# MB_DoorLock.net
KiCad netlist of a schematic drawn in EAGLE
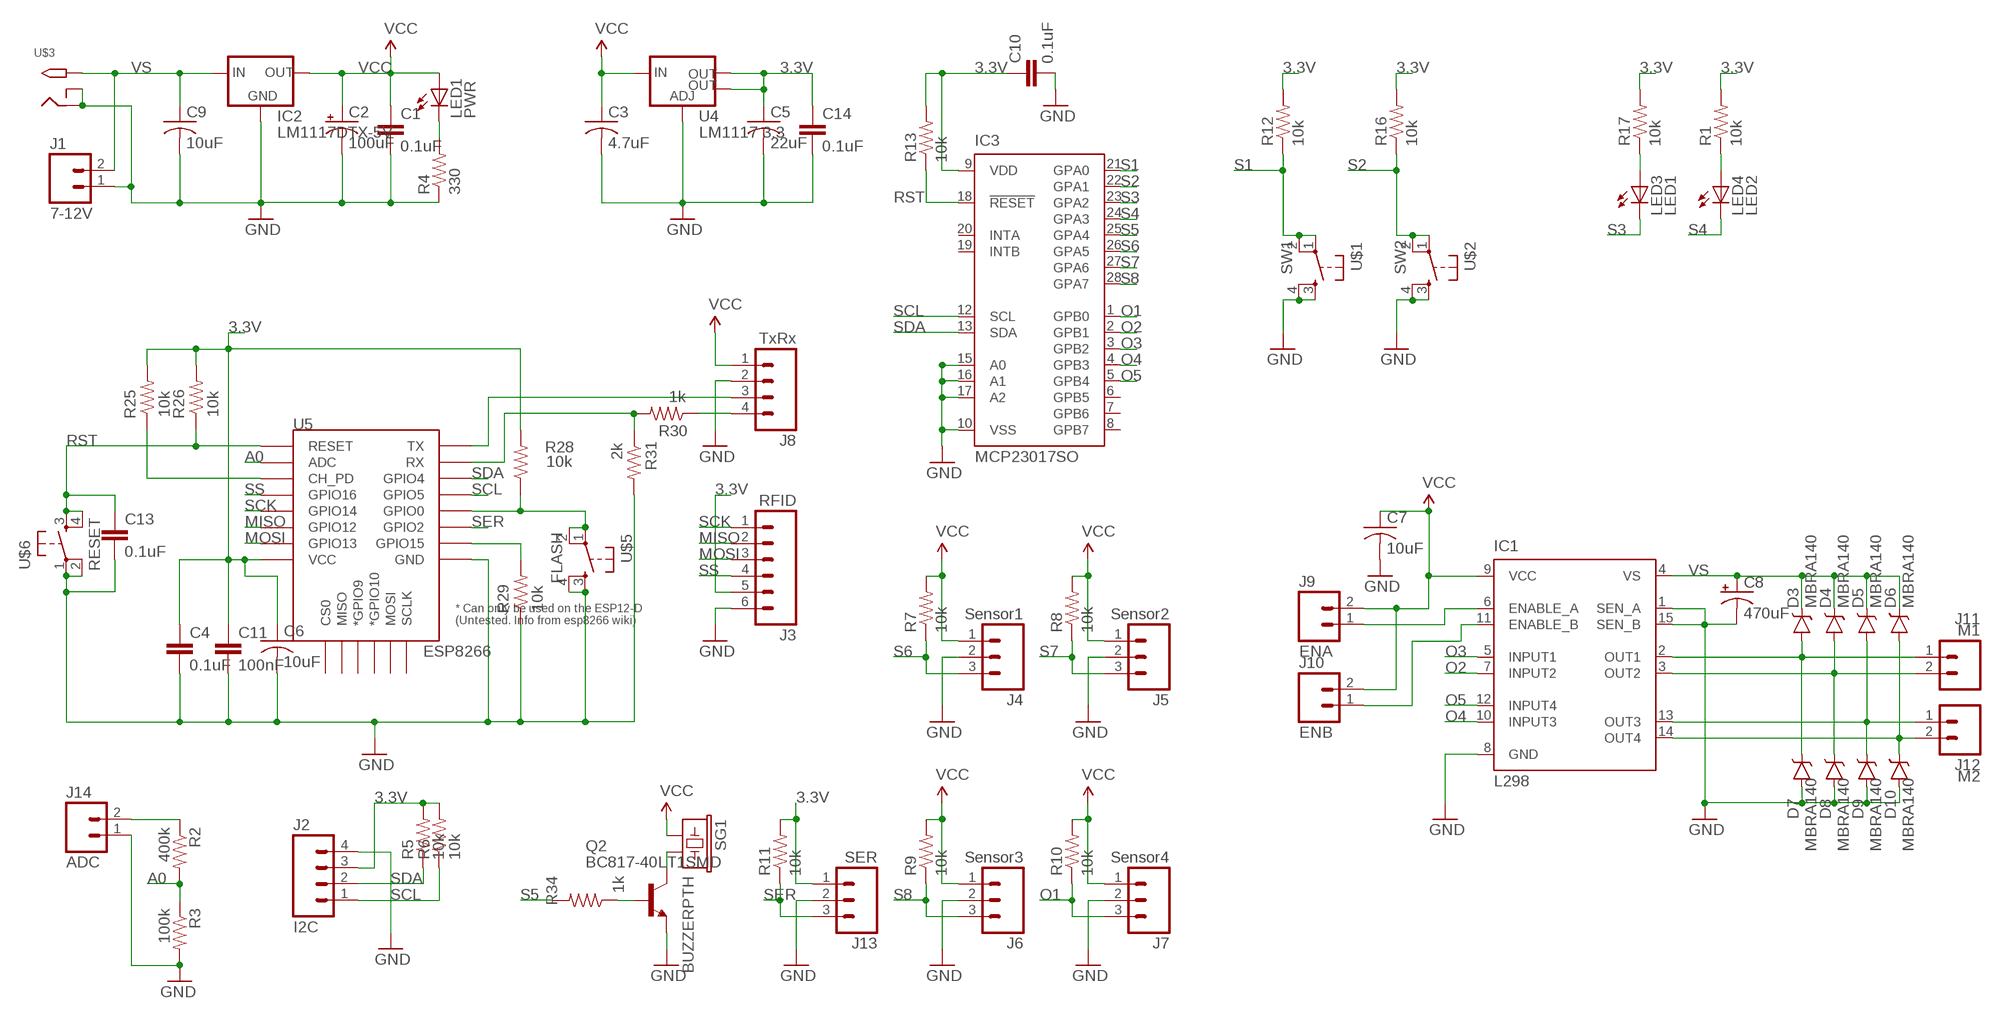
[diagram p0: schematic, sheet 1]

(export (version "E")
  (design (tool "Eeschema 10.0.6"))
  (components
    (comp (ref "C1")
      (value "0.1uF")
      (footprint "eagle-import:0805")
      (libsource (lib "eagle-import") (part "CAP0805"))
    )
    (comp (ref "C2")
      (value "100uF")
      (footprint "eagle-import:EIA3528-KIT")
      (libsource (lib "eagle-import") (part "CAP_POL3528-KIT"))
    )
    (comp (ref "C3")
      (value "4.7uF")
      (footprint "eagle-import:C1206")
      (libsource (lib "eagle-import") (part "C-USC1206"))
    )
    (comp (ref "C4")
      (value "0.1uF")
      (footprint "eagle-import:0805")
      (libsource (lib "eagle-import") (part "CAP0805"))
    )
    (comp (ref "C5")
      (value "22uF")
      (footprint "eagle-import:C1206")
      (libsource (lib "eagle-import") (part "C-USC1206"))
    )
    (comp (ref "C6")
      (value "10uF")
      (footprint "eagle-import:C1206")
      (libsource (lib "eagle-import") (part "C-USC1206"))
    )
    (comp (ref "C7")
      (value "10uF")
      (footprint "eagle-import:C1206")
      (libsource (lib "eagle-import") (part "C-USC1206"))
    )
    (comp (ref "C8")
      (value "470uF")
      (footprint "eagle-import:153CLV-1012")
      (libsource (lib "eagle-import") (part "CPOL-US153CLV-1012"))
    )
    (comp (ref "C9")
      (value "10uF")
      (footprint "eagle-import:C1206")
      (libsource (lib "eagle-import") (part "C-USC1206"))
    )
    (comp (ref "C10")
      (value "0.1uF")
      (footprint "eagle-import:0805")
      (libsource (lib "eagle-import") (part "CAP0805"))
    )
    (comp (ref "C11")
      (value "100nF")
      (footprint "eagle-import:0805")
      (libsource (lib "eagle-import") (part "CAP0805"))
    )
    (comp (ref "C13")
      (value "0.1uF")
      (footprint "eagle-import:0805")
      (libsource (lib "eagle-import") (part "CAP0805"))
    )
    (comp (ref "C14")
      (value "0.1uF")
      (footprint "eagle-import:0805")
      (libsource (lib "eagle-import") (part "CAP0805"))
    )
    (comp (ref "D3")
      (value "MBRA140")
      (footprint "eagle-import:SMA-DIODE")
      (libsource (lib "eagle-import") (part "MBRA140"))
    )
    (comp (ref "D4")
      (value "MBRA140")
      (footprint "eagle-import:SMA-DIODE")
      (libsource (lib "eagle-import") (part "MBRA140"))
    )
    (comp (ref "D5")
      (value "MBRA140")
      (footprint "eagle-import:SMA-DIODE")
      (libsource (lib "eagle-import") (part "MBRA140"))
    )
    (comp (ref "D6")
      (value "MBRA140")
      (footprint "eagle-import:SMA-DIODE")
      (libsource (lib "eagle-import") (part "MBRA140"))
    )
    (comp (ref "D7")
      (value "MBRA140")
      (footprint "eagle-import:SMA-DIODE")
      (libsource (lib "eagle-import") (part "MBRA140"))
    )
    (comp (ref "D8")
      (value "MBRA140")
      (footprint "eagle-import:SMA-DIODE")
      (libsource (lib "eagle-import") (part "MBRA140"))
    )
    (comp (ref "D9")
      (value "MBRA140")
      (footprint "eagle-import:SMA-DIODE")
      (libsource (lib "eagle-import") (part "MBRA140"))
    )
    (comp (ref "D10")
      (value "MBRA140")
      (footprint "eagle-import:SMA-DIODE")
      (libsource (lib "eagle-import") (part "MBRA140"))
    )
    (comp (ref "IC1")
      (value "L298")
      (footprint "eagle-import:MULTIWATT-15")
      (libsource (lib "eagle-import") (part "L298"))
    )
    (comp (ref "IC2")
      (value "LM1117DTX-5V")
      (footprint "eagle-import:TO252")
      (libsource (lib "eagle-import") (part "LM1117DTX-3.3"))
    )
    (comp (ref "IC3")
      (value "MCP23017SO")
      (footprint "eagle-import:SO28W")
      (fields (field (name "MF") "MICROCHIP") (field (name "MPN") "MCP23017-E/SO"))
      (libsource (lib "eagle-import") (part "MCP23017SO"))
    )
    (comp (ref "J1")
      (value "7-12V")
      (footprint "eagle-import:MOLEX-1X2")
      (libsource (lib "eagle-import") (part "M02POLAR"))
    )
    (comp (ref "J2")
      (value "I2C")
      (footprint "eagle-import:JST-4-PTH-VERT")
      (libsource (lib "eagle-import") (part "M04JST-PTH-VERT"))
    )
    (comp (ref "J3")
      (value "RFID")
      (footprint "eagle-import:MOLEX-1X6")
      (libsource (lib "eagle-import") (part "M06POLAR"))
    )
    (comp (ref "J4")
      (value "Sensor1")
      (footprint "eagle-import:JST-3-PTH-VERT")
      (libsource (lib "eagle-import") (part "M03JST-PTH-VERT"))
    )
    (comp (ref "J5")
      (value "Sensor2")
      (footprint "eagle-import:JST-3-PTH-VERT")
      (libsource (lib "eagle-import") (part "M03JST-PTH-VERT"))
    )
    (comp (ref "J6")
      (value "Sensor3")
      (footprint "eagle-import:JST-3-PTH-VERT")
      (libsource (lib "eagle-import") (part "M03JST-PTH-VERT"))
    )
    (comp (ref "J7")
      (value "Sensor4")
      (footprint "eagle-import:JST-3-PTH-VERT")
      (libsource (lib "eagle-import") (part "M03JST-PTH-VERT"))
    )
    (comp (ref "J8")
      (value "TxRx")
      (footprint "eagle-import:MOLEX-1X4")
      (libsource (lib "eagle-import") (part "M04POLAR"))
    )
    (comp (ref "J9")
      (value "ENA")
      (footprint "eagle-import:1X02")
      (libsource (lib "eagle-import") (part "M02PTH"))
    )
    (comp (ref "J10")
      (value "ENB")
      (footprint "eagle-import:1X02")
      (libsource (lib "eagle-import") (part "M02PTH"))
    )
    (comp (ref "J11")
      (value "M1")
      (footprint "eagle-import:MOLEX-1X2")
      (libsource (lib "eagle-import") (part "M02POLAR"))
    )
    (comp (ref "J12")
      (value "M2")
      (footprint "eagle-import:MOLEX-1X2")
      (libsource (lib "eagle-import") (part "M02POLAR"))
    )
    (comp (ref "J13")
      (value "SER")
      (footprint "eagle-import:JST-3-PTH-VERT")
      (libsource (lib "eagle-import") (part "M03JST-PTH-VERT"))
    )
    (comp (ref "J14")
      (value "ADC")
      (footprint "eagle-import:MOLEX-1X2")
      (libsource (lib "eagle-import") (part "M02POLAR"))
    )
    (comp (ref "LED1")
      (value "PWR")
      (footprint "eagle-import:CHIP-LED0805")
      (libsource (lib "eagle-import") (part "LEDCHIP-LED0805"))
    )
    (comp (ref "LED3")
      (value "LED1")
      (footprint "eagle-import:CHIP-LED0805")
      (libsource (lib "eagle-import") (part "LEDCHIP-LED0805"))
    )
    (comp (ref "LED4")
      (value "LED2")
      (footprint "eagle-import:CHIP-LED0805")
      (libsource (lib "eagle-import") (part "LEDCHIP-LED0805"))
    )
    (comp (ref "Q2")
      (value "BC817-40LT1SMD")
      (footprint "eagle-import:SOT23-BEC")
      (libsource (lib "eagle-import") (part "BC817SMD-40LT1"))
    )
    (comp (ref "R1")
      (value "10k")
      (footprint "eagle-import:0805")
      (libsource (lib "eagle-import") (part "RESISTOR0805-RES"))
    )
    (comp (ref "R2")
      (value "400k")
      (footprint "eagle-import:0805")
      (libsource (lib "eagle-import") (part "RESISTOR0805-RES"))
    )
    (comp (ref "R3")
      (value "100k")
      (footprint "eagle-import:0805")
      (libsource (lib "eagle-import") (part "RESISTOR0805-RES"))
    )
    (comp (ref "R4")
      (value "330")
      (footprint "eagle-import:0805")
      (libsource (lib "eagle-import") (part "RESISTOR0805-RES"))
    )
    (comp (ref "R5")
      (value "10k")
      (footprint "eagle-import:0805")
      (libsource (lib "eagle-import") (part "RESISTOR0805-RES"))
    )
    (comp (ref "R6")
      (value "10k")
      (footprint "eagle-import:0805")
      (libsource (lib "eagle-import") (part "RESISTOR0805-RES"))
    )
    (comp (ref "R7")
      (value "10k")
      (footprint "eagle-import:0805")
      (libsource (lib "eagle-import") (part "RESISTOR0805-RES"))
    )
    (comp (ref "R8")
      (value "10k")
      (footprint "eagle-import:0805")
      (libsource (lib "eagle-import") (part "RESISTOR0805-RES"))
    )
    (comp (ref "R9")
      (value "10k")
      (footprint "eagle-import:0805")
      (libsource (lib "eagle-import") (part "RESISTOR0805-RES"))
    )
    (comp (ref "R10")
      (value "10k")
      (footprint "eagle-import:0805")
      (libsource (lib "eagle-import") (part "RESISTOR0805-RES"))
    )
    (comp (ref "R11")
      (value "10k")
      (footprint "eagle-import:0805")
      (libsource (lib "eagle-import") (part "RESISTOR0805-RES"))
    )
    (comp (ref "R12")
      (value "10k")
      (footprint "eagle-import:0805")
      (libsource (lib "eagle-import") (part "RESISTOR0805-RES"))
    )
    (comp (ref "R13")
      (value "10k")
      (footprint "eagle-import:0805")
      (libsource (lib "eagle-import") (part "RESISTOR0805-RES"))
    )
    (comp (ref "R16")
      (value "10k")
      (footprint "eagle-import:0805")
      (libsource (lib "eagle-import") (part "RESISTOR0805-RES"))
    )
    (comp (ref "R17")
      (value "10k")
      (footprint "eagle-import:0805")
      (libsource (lib "eagle-import") (part "RESISTOR0805-RES"))
    )
    (comp (ref "R25")
      (value "10k")
      (footprint "eagle-import:0805")
      (libsource (lib "eagle-import") (part "RESISTOR0805-RES"))
    )
    (comp (ref "R26")
      (value "10k")
      (footprint "eagle-import:0805")
      (libsource (lib "eagle-import") (part "RESISTOR0805-RES"))
    )
    (comp (ref "R28")
      (value "10k")
      (footprint "eagle-import:0805")
      (libsource (lib "eagle-import") (part "RESISTOR0805-RES"))
    )
    (comp (ref "R29")
      (value "10k")
      (footprint "eagle-import:0805")
      (libsource (lib "eagle-import") (part "RESISTOR0805-RES"))
    )
    (comp (ref "R30")
      (value "1k")
      (footprint "eagle-import:0805")
      (libsource (lib "eagle-import") (part "RESISTOR0805-RES"))
    )
    (comp (ref "R31")
      (value "2k")
      (footprint "eagle-import:0805")
      (libsource (lib "eagle-import") (part "RESISTOR0805-RES"))
    )
    (comp (ref "R34")
      (value "1k")
      (footprint "eagle-import:0805")
      (libsource (lib "eagle-import") (part "RESISTOR0805-RES"))
    )
    (comp (ref "SG1")
      (value "BUZZERPTH")
      (footprint "eagle-import:BUZZER-12MM")
      (libsource (lib "eagle-import") (part "BUZZERPTH"))
    )
    (comp (ref "U$1")
      (value "SW1")
      (footprint "eagle-import:TAC-SWITCH-PTH")
      (libsource (lib "eagle-import") (part "TACTILE-SWITCH-PTH"))
    )
    (comp (ref "U$2")
      (value "SW2")
      (footprint "eagle-import:TAC-SWITCH-PTH")
      (libsource (lib "eagle-import") (part "TACTILE-SWITCH-PTH"))
    )
    (comp (ref "U$3")
      (value "7*12V")
      (footprint "eagle-import:PJ-102A")
      (libsource (lib "eagle-import") (part "2.1MMJACK"))
    )
    (comp (ref "U$5")
      (value "FLASH")
      (footprint "eagle-import:TAC-SWITCH-PTH")
      (libsource (lib "eagle-import") (part "TACTILE-SWITCH-PTH"))
    )
    (comp (ref "U$6")
      (value "RESET")
      (footprint "eagle-import:TAC-SWITCH-PTH")
      (libsource (lib "eagle-import") (part "TACTILE-SWITCH-PTH"))
    )
    (comp (ref "U4")
      (value "LM1117 3.3")
      (footprint "eagle-import:SOT223")
      (libsource (lib "eagle-import") (part "V_REG_LM1117SOT223"))
    )
    (comp (ref "U5")
      (value "ESP8266")
      (footprint "eagle-import:ESP12E-SMD")
      (libsource (lib "eagle-import") (part "ESP12ESMD"))
    )
  )
  (nets
    (net (code "1") (name "/3.3V") (class "Default")
      (node (ref "C10") (pin "1") (pinfunction "1_1") (pintype "passive"))
      (node (ref "C11") (pin "1") (pinfunction "1_1") (pintype "passive"))
      (node (ref "C14") (pin "1") (pinfunction "1_1") (pintype "passive"))
      (node (ref "C4") (pin "1") (pinfunction "1_1") (pintype "passive"))
      (node (ref "C5") (pin "1") (pinfunction "1_1") (pintype "passive"))
      (node (ref "C6") (pin "1") (pinfunction "1_1") (pintype "passive"))
      (node (ref "IC3") (pin "9") (pinfunction "VDD_9") (pintype "power_in"))
      (node (ref "J13") (pin "1") (pinfunction "1_1") (pintype "passive"))
      (node (ref "J2") (pin "3") (pinfunction "3_3") (pintype "passive"))
      (node (ref "J3") (pin "5") (pinfunction "5_5") (pintype "passive"))
      (node (ref "R1") (pin "2") (pinfunction "2_2") (pintype "passive"))
      (node (ref "R11") (pin "2") (pinfunction "2_2") (pintype "passive"))
      (node (ref "R12") (pin "2") (pinfunction "2_2") (pintype "passive"))
      (node (ref "R13") (pin "2") (pinfunction "2_2") (pintype "passive"))
      (node (ref "R16") (pin "2") (pinfunction "2_2") (pintype "passive"))
      (node (ref "R17") (pin "2") (pinfunction "2_2") (pintype "passive"))
      (node (ref "R25") (pin "2") (pinfunction "2_2") (pintype "passive"))
      (node (ref "R26") (pin "2") (pinfunction "2_2") (pintype "passive"))
      (node (ref "R28") (pin "2") (pinfunction "2_2") (pintype "passive"))
      (node (ref "R5") (pin "2") (pinfunction "2_2") (pintype "passive"))
      (node (ref "R6") (pin "2") (pinfunction "2_2") (pintype "passive"))
      (node (ref "U4") (pin "2") (pinfunction "OUT_2") (pintype "output"))
      (node (ref "U4") (pin "4") (pinfunction "OUT_4") (pintype "output"))
      (node (ref "U5") (pin "VCC") (pinfunction "VCC_VCC") (pintype "bidirectional"))
    )
    (net (code "2") (name "/A0") (class "Default")
      (node (ref "R2") (pin "2") (pinfunction "2_2") (pintype "passive"))
      (node (ref "R3") (pin "1") (pinfunction "1_1") (pintype "passive"))
      (node (ref "U5") (pin "ADC") (pinfunction "ADC_ADC") (pintype "bidirectional"))
    )
    (net (code "3") (name "/MISO") (class "Default")
      (node (ref "J3") (pin "2") (pinfunction "2_2") (pintype "passive"))
      (node (ref "U5") (pin "GPIO12") (pinfunction "GPIO12_GPIO12") (pintype "bidirectional"))
    )
    (net (code "4") (name "/MOSI") (class "Default")
      (node (ref "J3") (pin "3") (pinfunction "3_3") (pintype "passive"))
      (node (ref "U5") (pin "GPIO13") (pinfunction "GPIO13_GPIO13") (pintype "bidirectional"))
    )
    (net (code "5") (name "/O1") (class "Default")
      (node (ref "IC3") (pin "1") (pinfunction "GPB0_1") (pintype "bidirectional"))
      (node (ref "J7") (pin "3") (pinfunction "3_3") (pintype "passive"))
      (node (ref "R10") (pin "1") (pinfunction "1_1") (pintype "passive"))
    )
    (net (code "6") (name "/O2") (class "Default")
      (node (ref "IC1") (pin "7") (pinfunction "INPUT2_7") (pintype "input"))
      (node (ref "IC3") (pin "2") (pinfunction "GPB1_2") (pintype "bidirectional"))
    )
    (net (code "7") (name "/O3") (class "Default")
      (node (ref "IC1") (pin "5") (pinfunction "INPUT1_5") (pintype "input"))
      (node (ref "IC3") (pin "3") (pinfunction "GPB2_3") (pintype "bidirectional"))
    )
    (net (code "8") (name "/O4") (class "Default")
      (node (ref "IC1") (pin "10") (pinfunction "INPUT3_10") (pintype "input"))
      (node (ref "IC3") (pin "4") (pinfunction "GPB3_4") (pintype "bidirectional"))
    )
    (net (code "9") (name "/O5") (class "Default")
      (node (ref "IC1") (pin "12") (pinfunction "INPUT4_12") (pintype "input"))
      (node (ref "IC3") (pin "5") (pinfunction "GPB4_5") (pintype "bidirectional"))
    )
    (net (code "10") (name "/RST") (class "Default")
      (node (ref "C13") (pin "1") (pinfunction "1_1") (pintype "passive"))
      (node (ref "IC3") (pin "18") (pinfunction "~{RESET}_18") (pintype "input"))
      (node (ref "R13") (pin "1") (pinfunction "1_1") (pintype "passive"))
      (node (ref "R26") (pin "1") (pinfunction "1_1") (pintype "passive"))
      (node (ref "U$6") (pin "3") (pinfunction "3_3") (pintype "passive"))
      (node (ref "U$6") (pin "4") (pinfunction "4_4") (pintype "passive"))
      (node (ref "U5") (pin "RESET") (pinfunction "RESET_RESET") (pintype "bidirectional"))
    )
    (net (code "11") (name "/S1") (class "Default")
      (node (ref "IC3") (pin "21") (pinfunction "GPA0_21") (pintype "bidirectional"))
      (node (ref "R12") (pin "1") (pinfunction "1_1") (pintype "passive"))
      (node (ref "U$1") (pin "1") (pinfunction "1_1") (pintype "passive"))
      (node (ref "U$1") (pin "2") (pinfunction "2_2") (pintype "passive"))
    )
    (net (code "12") (name "/S2") (class "Default")
      (node (ref "IC3") (pin "22") (pinfunction "GPA1_22") (pintype "bidirectional"))
      (node (ref "R16") (pin "1") (pinfunction "1_1") (pintype "passive"))
      (node (ref "U$2") (pin "1") (pinfunction "1_1") (pintype "passive"))
      (node (ref "U$2") (pin "2") (pinfunction "2_2") (pintype "passive"))
    )
    (net (code "13") (name "/S3") (class "Default")
      (node (ref "IC3") (pin "23") (pinfunction "GPA2_23") (pintype "bidirectional"))
      (node (ref "LED3") (pin "C") (pinfunction "C_C") (pintype "passive"))
    )
    (net (code "14") (name "/S4") (class "Default")
      (node (ref "IC3") (pin "24") (pinfunction "GPA3_24") (pintype "bidirectional"))
      (node (ref "LED4") (pin "C") (pinfunction "C_C") (pintype "passive"))
    )
    (net (code "15") (name "/S5") (class "Default")
      (node (ref "IC3") (pin "25") (pinfunction "GPA4_25") (pintype "bidirectional"))
      (node (ref "R34") (pin "2") (pinfunction "2_2") (pintype "passive"))
    )
    (net (code "16") (name "/S6") (class "Default")
      (node (ref "IC3") (pin "26") (pinfunction "GPA5_26") (pintype "bidirectional"))
      (node (ref "J4") (pin "3") (pinfunction "3_3") (pintype "passive"))
      (node (ref "R7") (pin "1") (pinfunction "1_1") (pintype "passive"))
    )
    (net (code "17") (name "/S7") (class "Default")
      (node (ref "IC3") (pin "27") (pinfunction "GPA6_27") (pintype "bidirectional"))
      (node (ref "J5") (pin "3") (pinfunction "3_3") (pintype "passive"))
      (node (ref "R8") (pin "1") (pinfunction "1_1") (pintype "passive"))
    )
    (net (code "18") (name "/S8") (class "Default")
      (node (ref "IC3") (pin "28") (pinfunction "GPA7_28") (pintype "bidirectional"))
      (node (ref "J6") (pin "3") (pinfunction "3_3") (pintype "passive"))
      (node (ref "R9") (pin "1") (pinfunction "1_1") (pintype "passive"))
    )
    (net (code "19") (name "/SCK") (class "Default")
      (node (ref "J3") (pin "1") (pinfunction "1_1") (pintype "passive"))
      (node (ref "U5") (pin "GPIO14") (pinfunction "GPIO14_GPIO14") (pintype "bidirectional"))
    )
    (net (code "20") (name "/SCL") (class "Default")
      (node (ref "IC3") (pin "12") (pinfunction "SCL_12") (pintype "input"))
      (node (ref "J2") (pin "1") (pinfunction "1_1") (pintype "passive"))
      (node (ref "R6") (pin "1") (pinfunction "1_1") (pintype "passive"))
      (node (ref "U5") (pin "GPIO5") (pinfunction "GPIO5_GPIO5") (pintype "bidirectional"))
    )
    (net (code "21") (name "/SDA") (class "Default")
      (node (ref "IC3") (pin "13") (pinfunction "SDA_13") (pintype "bidirectional"))
      (node (ref "J2") (pin "2") (pinfunction "2_2") (pintype "passive"))
      (node (ref "R5") (pin "1") (pinfunction "1_1") (pintype "passive"))
      (node (ref "U5") (pin "GPIO4") (pinfunction "GPIO4_GPIO4") (pintype "bidirectional"))
    )
    (net (code "22") (name "/SER") (class "Default")
      (node (ref "J13") (pin "3") (pinfunction "3_3") (pintype "passive"))
      (node (ref "R11") (pin "1") (pinfunction "1_1") (pintype "passive"))
      (node (ref "U5") (pin "GPIO2") (pinfunction "GPIO2_GPIO2") (pintype "bidirectional"))
    )
    (net (code "23") (name "/SS") (class "Default")
      (node (ref "J3") (pin "4") (pinfunction "4_4") (pintype "passive"))
      (node (ref "U5") (pin "GPIO16") (pinfunction "GPIO16_GPIO16") (pintype "bidirectional"))
    )
    (net (code "24") (name "/VS") (class "Default")
      (node (ref "C8") (pin "+") (pinfunction "+_+") (pintype "passive"))
      (node (ref "C9") (pin "1") (pinfunction "1_1") (pintype "passive"))
      (node (ref "D3") (pin "C") (pinfunction "C_C") (pintype "passive"))
      (node (ref "D4") (pin "C") (pinfunction "C_C") (pintype "passive"))
      (node (ref "D5") (pin "C") (pinfunction "C_C") (pintype "passive"))
      (node (ref "D6") (pin "C") (pinfunction "C_C") (pintype "passive"))
      (node (ref "IC1") (pin "4") (pinfunction "VS_4") (pintype "power_in"))
      (node (ref "IC2") (pin "2") (pinfunction "IN_2") (pintype "input"))
      (node (ref "J1") (pin "2") (pinfunction "2_2") (pintype "passive"))
      (node (ref "U$3") (pin "TIP") (pinfunction "TIP_TIP") (pintype "bidirectional"))
    )
    (net (code "25") (name "GND") (class "Default")
      (node (ref "C1") (pin "2") (pinfunction "2_2") (pintype "passive"))
      (node (ref "C10") (pin "2") (pinfunction "2_2") (pintype "passive"))
      (node (ref "C11") (pin "2") (pinfunction "2_2") (pintype "passive"))
      (node (ref "C13") (pin "2") (pinfunction "2_2") (pintype "passive"))
      (node (ref "C14") (pin "2") (pinfunction "2_2") (pintype "passive"))
      (node (ref "C2") (pin "C") (pinfunction "-_C") (pintype "passive"))
      (node (ref "C3") (pin "2") (pinfunction "2_2") (pintype "passive"))
      (node (ref "C4") (pin "2") (pinfunction "2_2") (pintype "passive"))
      (node (ref "C5") (pin "2") (pinfunction "2_2") (pintype "passive"))
      (node (ref "C6") (pin "2") (pinfunction "2_2") (pintype "passive"))
      (node (ref "C7") (pin "2") (pinfunction "2_2") (pintype "passive"))
      (node (ref "C8") (pin "-") (pinfunction "-_-") (pintype "passive"))
      (node (ref "C9") (pin "2") (pinfunction "2_2") (pintype "passive"))
      (node (ref "D10") (pin "A") (pinfunction "A_A") (pintype "passive"))
      (node (ref "D7") (pin "A") (pinfunction "A_A") (pintype "passive"))
      (node (ref "D8") (pin "A") (pinfunction "A_A") (pintype "passive"))
      (node (ref "D9") (pin "A") (pinfunction "A_A") (pintype "passive"))
      (node (ref "IC1") (pin "1") (pinfunction "SEN_A_1") (pintype "input"))
      (node (ref "IC1") (pin "15") (pinfunction "SEN_B_15") (pintype "input"))
      (node (ref "IC1") (pin "8") (pinfunction "GND_8") (pintype "power_in"))
      (node (ref "IC2") (pin "1") (pinfunction "GND_1") (pintype "input"))
      (node (ref "IC3") (pin "10") (pinfunction "VSS_10") (pintype "power_in"))
      (node (ref "IC3") (pin "15") (pinfunction "A0_15") (pintype "input"))
      (node (ref "IC3") (pin "16") (pinfunction "A1_16") (pintype "input"))
      (node (ref "IC3") (pin "17") (pinfunction "A2_17") (pintype "input"))
      (node (ref "J1") (pin "1") (pinfunction "1_1") (pintype "passive"))
      (node (ref "J13") (pin "2") (pinfunction "2_2") (pintype "passive"))
      (node (ref "J14") (pin "1") (pinfunction "1_1") (pintype "passive"))
      (node (ref "J2") (pin "4") (pinfunction "4_4") (pintype "passive"))
      (node (ref "J3") (pin "6") (pinfunction "6_6") (pintype "passive"))
      (node (ref "J4") (pin "2") (pinfunction "2_2") (pintype "passive"))
      (node (ref "J5") (pin "2") (pinfunction "2_2") (pintype "passive"))
      (node (ref "J6") (pin "2") (pinfunction "2_2") (pintype "passive"))
      (node (ref "J7") (pin "2") (pinfunction "2_2") (pintype "passive"))
      (node (ref "J8") (pin "2") (pinfunction "2_2") (pintype "passive"))
      (node (ref "Q2") (pin "E") (pinfunction "E_E") (pintype "passive"))
      (node (ref "R29") (pin "1") (pinfunction "1_1") (pintype "passive"))
      (node (ref "R3") (pin "2") (pinfunction "2_2") (pintype "passive"))
      (node (ref "R31") (pin "2") (pinfunction "2_2") (pintype "passive"))
      (node (ref "R4") (pin "1") (pinfunction "1_1") (pintype "passive"))
      (node (ref "U$1") (pin "3") (pinfunction "3_3") (pintype "passive"))
      (node (ref "U$1") (pin "4") (pinfunction "4_4") (pintype "passive"))
      (node (ref "U$2") (pin "3") (pinfunction "3_3") (pintype "passive"))
      (node (ref "U$2") (pin "4") (pinfunction "4_4") (pintype "passive"))
      (node (ref "U$3") (pin "RING") (pinfunction "RING_RING") (pintype "bidirectional"))
      (node (ref "U$3") (pin "RING_SW") (pinfunction "RING_SW_RING_SW") (pintype "bidirectional"))
      (node (ref "U$5") (pin "3") (pinfunction "3_3") (pintype "passive"))
      (node (ref "U$5") (pin "4") (pinfunction "4_4") (pintype "passive"))
      (node (ref "U$6") (pin "1") (pinfunction "1_1") (pintype "passive"))
      (node (ref "U$6") (pin "2") (pinfunction "2_2") (pintype "passive"))
      (node (ref "U4") (pin "1") (pinfunction "ADJ_1") (pintype "input"))
      (node (ref "U5") (pin "GND") (pinfunction "GND_GND") (pintype "bidirectional"))
    )
    (net (code "26") (name "Net-(IC1-ENABLE_A)") (class "Default")
      (node (ref "IC1") (pin "6") (pinfunction "ENABLE_A_6") (pintype "input"))
      (node (ref "J9") (pin "1") (pinfunction "1_1") (pintype "passive"))
    )
    (net (code "27") (name "Net-(IC1-ENABLE_B)") (class "Default")
      (node (ref "IC1") (pin "11") (pinfunction "ENABLE_B_11") (pintype "input"))
      (node (ref "J10") (pin "1") (pinfunction "1_1") (pintype "passive"))
    )
    (net (code "28") (name "Net-(IC1-OUT1)") (class "Default")
      (node (ref "D3") (pin "A") (pinfunction "A_A") (pintype "passive"))
      (node (ref "D7") (pin "C") (pinfunction "C_C") (pintype "passive"))
      (node (ref "IC1") (pin "2") (pinfunction "OUT1_2") (pintype "output"))
      (node (ref "J11") (pin "1") (pinfunction "1_1") (pintype "passive"))
    )
    (net (code "29") (name "Net-(IC1-OUT2)") (class "Default")
      (node (ref "D4") (pin "A") (pinfunction "A_A") (pintype "passive"))
      (node (ref "D8") (pin "C") (pinfunction "C_C") (pintype "passive"))
      (node (ref "IC1") (pin "3") (pinfunction "OUT2_3") (pintype "output"))
      (node (ref "J11") (pin "2") (pinfunction "2_2") (pintype "passive"))
    )
    (net (code "30") (name "Net-(IC1-OUT3)") (class "Default")
      (node (ref "D5") (pin "A") (pinfunction "A_A") (pintype "passive"))
      (node (ref "D9") (pin "C") (pinfunction "C_C") (pintype "passive"))
      (node (ref "IC1") (pin "13") (pinfunction "OUT3_13") (pintype "output"))
      (node (ref "J12") (pin "1") (pinfunction "1_1") (pintype "passive"))
    )
    (net (code "31") (name "Net-(IC1-OUT4)") (class "Default")
      (node (ref "D10") (pin "C") (pinfunction "C_C") (pintype "passive"))
      (node (ref "D6") (pin "A") (pinfunction "A_A") (pintype "passive"))
      (node (ref "IC1") (pin "14") (pinfunction "OUT4_14") (pintype "output"))
      (node (ref "J12") (pin "2") (pinfunction "2_2") (pintype "passive"))
    )
    (net (code "32") (name "Net-(J8-Pad4)") (class "Default")
      (node (ref "J8") (pin "4") (pinfunction "4_4") (pintype "passive"))
      (node (ref "R30") (pin "1") (pinfunction "1_1") (pintype "passive"))
    )
    (net (code "33") (name "Net-(J14-Pad2)") (class "Default")
      (node (ref "J14") (pin "2") (pinfunction "2_2") (pintype "passive"))
      (node (ref "R2") (pin "1") (pinfunction "1_1") (pintype "passive"))
    )
    (net (code "34") (name "Net-(LED1-PadC)") (class "Default")
      (node (ref "LED1") (pin "C") (pinfunction "C_C") (pintype "passive"))
      (node (ref "R4") (pin "2") (pinfunction "2_2") (pintype "passive"))
    )
    (net (code "35") (name "Net-(LED3-PadA)") (class "Default")
      (node (ref "LED3") (pin "A") (pinfunction "A_A") (pintype "passive"))
      (node (ref "R17") (pin "1") (pinfunction "1_1") (pintype "passive"))
    )
    (net (code "36") (name "Net-(LED4-PadA)") (class "Default")
      (node (ref "LED4") (pin "A") (pinfunction "A_A") (pintype "passive"))
      (node (ref "R1") (pin "1") (pinfunction "1_1") (pintype "passive"))
    )
    (net (code "37") (name "Net-(Q2-PadB)") (class "Default")
      (node (ref "Q2") (pin "B") (pinfunction "B_B") (pintype "passive"))
      (node (ref "R34") (pin "1") (pinfunction "1_1") (pintype "passive"))
    )
    (net (code "38") (name "Net-(R25-Pad1)") (class "Default")
      (node (ref "R25") (pin "1") (pinfunction "1_1") (pintype "passive"))
      (node (ref "U5") (pin "CH_PD") (pinfunction "CH_PD_CH_PD") (pintype "bidirectional"))
    )
    (net (code "39") (name "Net-(R28-Pad1)") (class "Default")
      (node (ref "R28") (pin "1") (pinfunction "1_1") (pintype "passive"))
      (node (ref "U$5") (pin "1") (pinfunction "1_1") (pintype "passive"))
      (node (ref "U$5") (pin "2") (pinfunction "2_2") (pintype "passive"))
      (node (ref "U5") (pin "GPIO0") (pinfunction "GPIO0_GPIO0") (pintype "bidirectional"))
    )
    (net (code "40") (name "Net-(R29-Pad2)") (class "Default")
      (node (ref "R29") (pin "2") (pinfunction "2_2") (pintype "passive"))
      (node (ref "U5") (pin "GPIO15") (pinfunction "GPIO15_GPIO15") (pintype "bidirectional"))
    )
    (net (code "41") (name "Net-(SG1-2)") (class "Default")
      (node (ref "Q2") (pin "C") (pinfunction "C_C") (pintype "passive"))
      (node (ref "SG1") (pin "-") (pinfunction "2_-") (pintype "passive"))
    )
    (net (code "42") (name "Net-(U5-RX)") (class "Default")
      (node (ref "R30") (pin "2") (pinfunction "2_2") (pintype "passive"))
      (node (ref "R31") (pin "1") (pinfunction "1_1") (pintype "passive"))
      (node (ref "U5") (pin "RXD0") (pinfunction "RX_RXD0") (pintype "bidirectional"))
    )
    (net (code "43") (name "Net-(U5-TX)") (class "Default")
      (node (ref "J8") (pin "3") (pinfunction "3_3") (pintype "passive"))
      (node (ref "U5") (pin "TXD0") (pinfunction "TX_TXD0") (pintype "bidirectional"))
    )
    (net (code "44") (name "VCC") (class "Default")
      (node (ref "C1") (pin "1") (pinfunction "1_1") (pintype "passive"))
      (node (ref "C2") (pin "A") (pinfunction "+_A") (pintype "passive"))
      (node (ref "C3") (pin "1") (pinfunction "1_1") (pintype "passive"))
      (node (ref "C7") (pin "1") (pinfunction "1_1") (pintype "passive"))
      (node (ref "IC1") (pin "9") (pinfunction "VCC_9") (pintype "power_in"))
      (node (ref "IC2") (pin "TAB") (pinfunction "OUT_TAB") (pintype "passive"))
      (node (ref "J10") (pin "2") (pinfunction "2_2") (pintype "passive"))
      (node (ref "J4") (pin "1") (pinfunction "1_1") (pintype "passive"))
      (node (ref "J5") (pin "1") (pinfunction "1_1") (pintype "passive"))
      (node (ref "J6") (pin "1") (pinfunction "1_1") (pintype "passive"))
      (node (ref "J7") (pin "1") (pinfunction "1_1") (pintype "passive"))
      (node (ref "J8") (pin "1") (pinfunction "1_1") (pintype "passive"))
      (node (ref "J9") (pin "2") (pinfunction "2_2") (pintype "passive"))
      (node (ref "LED1") (pin "A") (pinfunction "A_A") (pintype "passive"))
      (node (ref "R10") (pin "2") (pinfunction "2_2") (pintype "passive"))
      (node (ref "R7") (pin "2") (pinfunction "2_2") (pintype "passive"))
      (node (ref "R8") (pin "2") (pinfunction "2_2") (pintype "passive"))
      (node (ref "R9") (pin "2") (pinfunction "2_2") (pintype "passive"))
      (node (ref "SG1") (pin "+") (pinfunction "1_+") (pintype "passive"))
      (node (ref "U4") (pin "3") (pinfunction "IN_3") (pintype "input"))
    )
    (net (code "45") (name "unconnected-(IC3-GPB5-Pad6)") (class "Default")
      (node (ref "IC3") (pin "6") (pinfunction "GPB5_6") (pintype "bidirectional"))
    )
    (net (code "46") (name "unconnected-(IC3-GPB6-Pad7)") (class "Default")
      (node (ref "IC3") (pin "7") (pinfunction "GPB6_7") (pintype "bidirectional"))
    )
    (net (code "47") (name "unconnected-(IC3-GPB7-Pad8)") (class "Default")
      (node (ref "IC3") (pin "8") (pinfunction "GPB7_8") (pintype "bidirectional"))
    )
    (net (code "48") (name "unconnected-(IC3-INTA-Pad20)") (class "Default")
      (node (ref "IC3") (pin "20") (pinfunction "INTA_20") (pintype "output"))
    )
    (net (code "49") (name "unconnected-(IC3-INTB-Pad19)") (class "Default")
      (node (ref "IC3") (pin "19") (pinfunction "INTB_19") (pintype "output"))
    )
    (net (code "50") (name "unconnected-(U5-*GPIO9-PadGPIO9)") (class "Default")
      (node (ref "U5") (pin "GPIO9") (pinfunction "*GPIO9_GPIO9") (pintype "bidirectional"))
    )
    (net (code "51") (name "unconnected-(U5-*GPIO10-PadGPIO10)") (class "Default")
      (node (ref "U5") (pin "GPIO10") (pinfunction "*GPIO10_GPIO10") (pintype "bidirectional"))
    )
    (net (code "52") (name "unconnected-(U5-PadCS0)") (class "Default")
      (node (ref "U5") (pin "CS0") (pinfunction "CS0_CS0") (pintype "bidirectional"))
    )
    (net (code "53") (name "unconnected-(U5-PadMISO)") (class "Default")
      (node (ref "U5") (pin "MISO") (pinfunction "MISO_MISO") (pintype "bidirectional"))
    )
    (net (code "54") (name "unconnected-(U5-PadMOSI)") (class "Default")
      (node (ref "U5") (pin "MOSI") (pinfunction "MOSI_MOSI") (pintype "bidirectional"))
    )
    (net (code "55") (name "unconnected-(U5-PadSCLK)") (class "Default")
      (node (ref "U5") (pin "SCLK") (pinfunction "SCLK_SCLK") (pintype "bidirectional"))
    )
  )
)
